# ProPrj_pico_debugger_2026-04-05.net
KiCad netlist of a schematic drawn in EasyEDA Pro
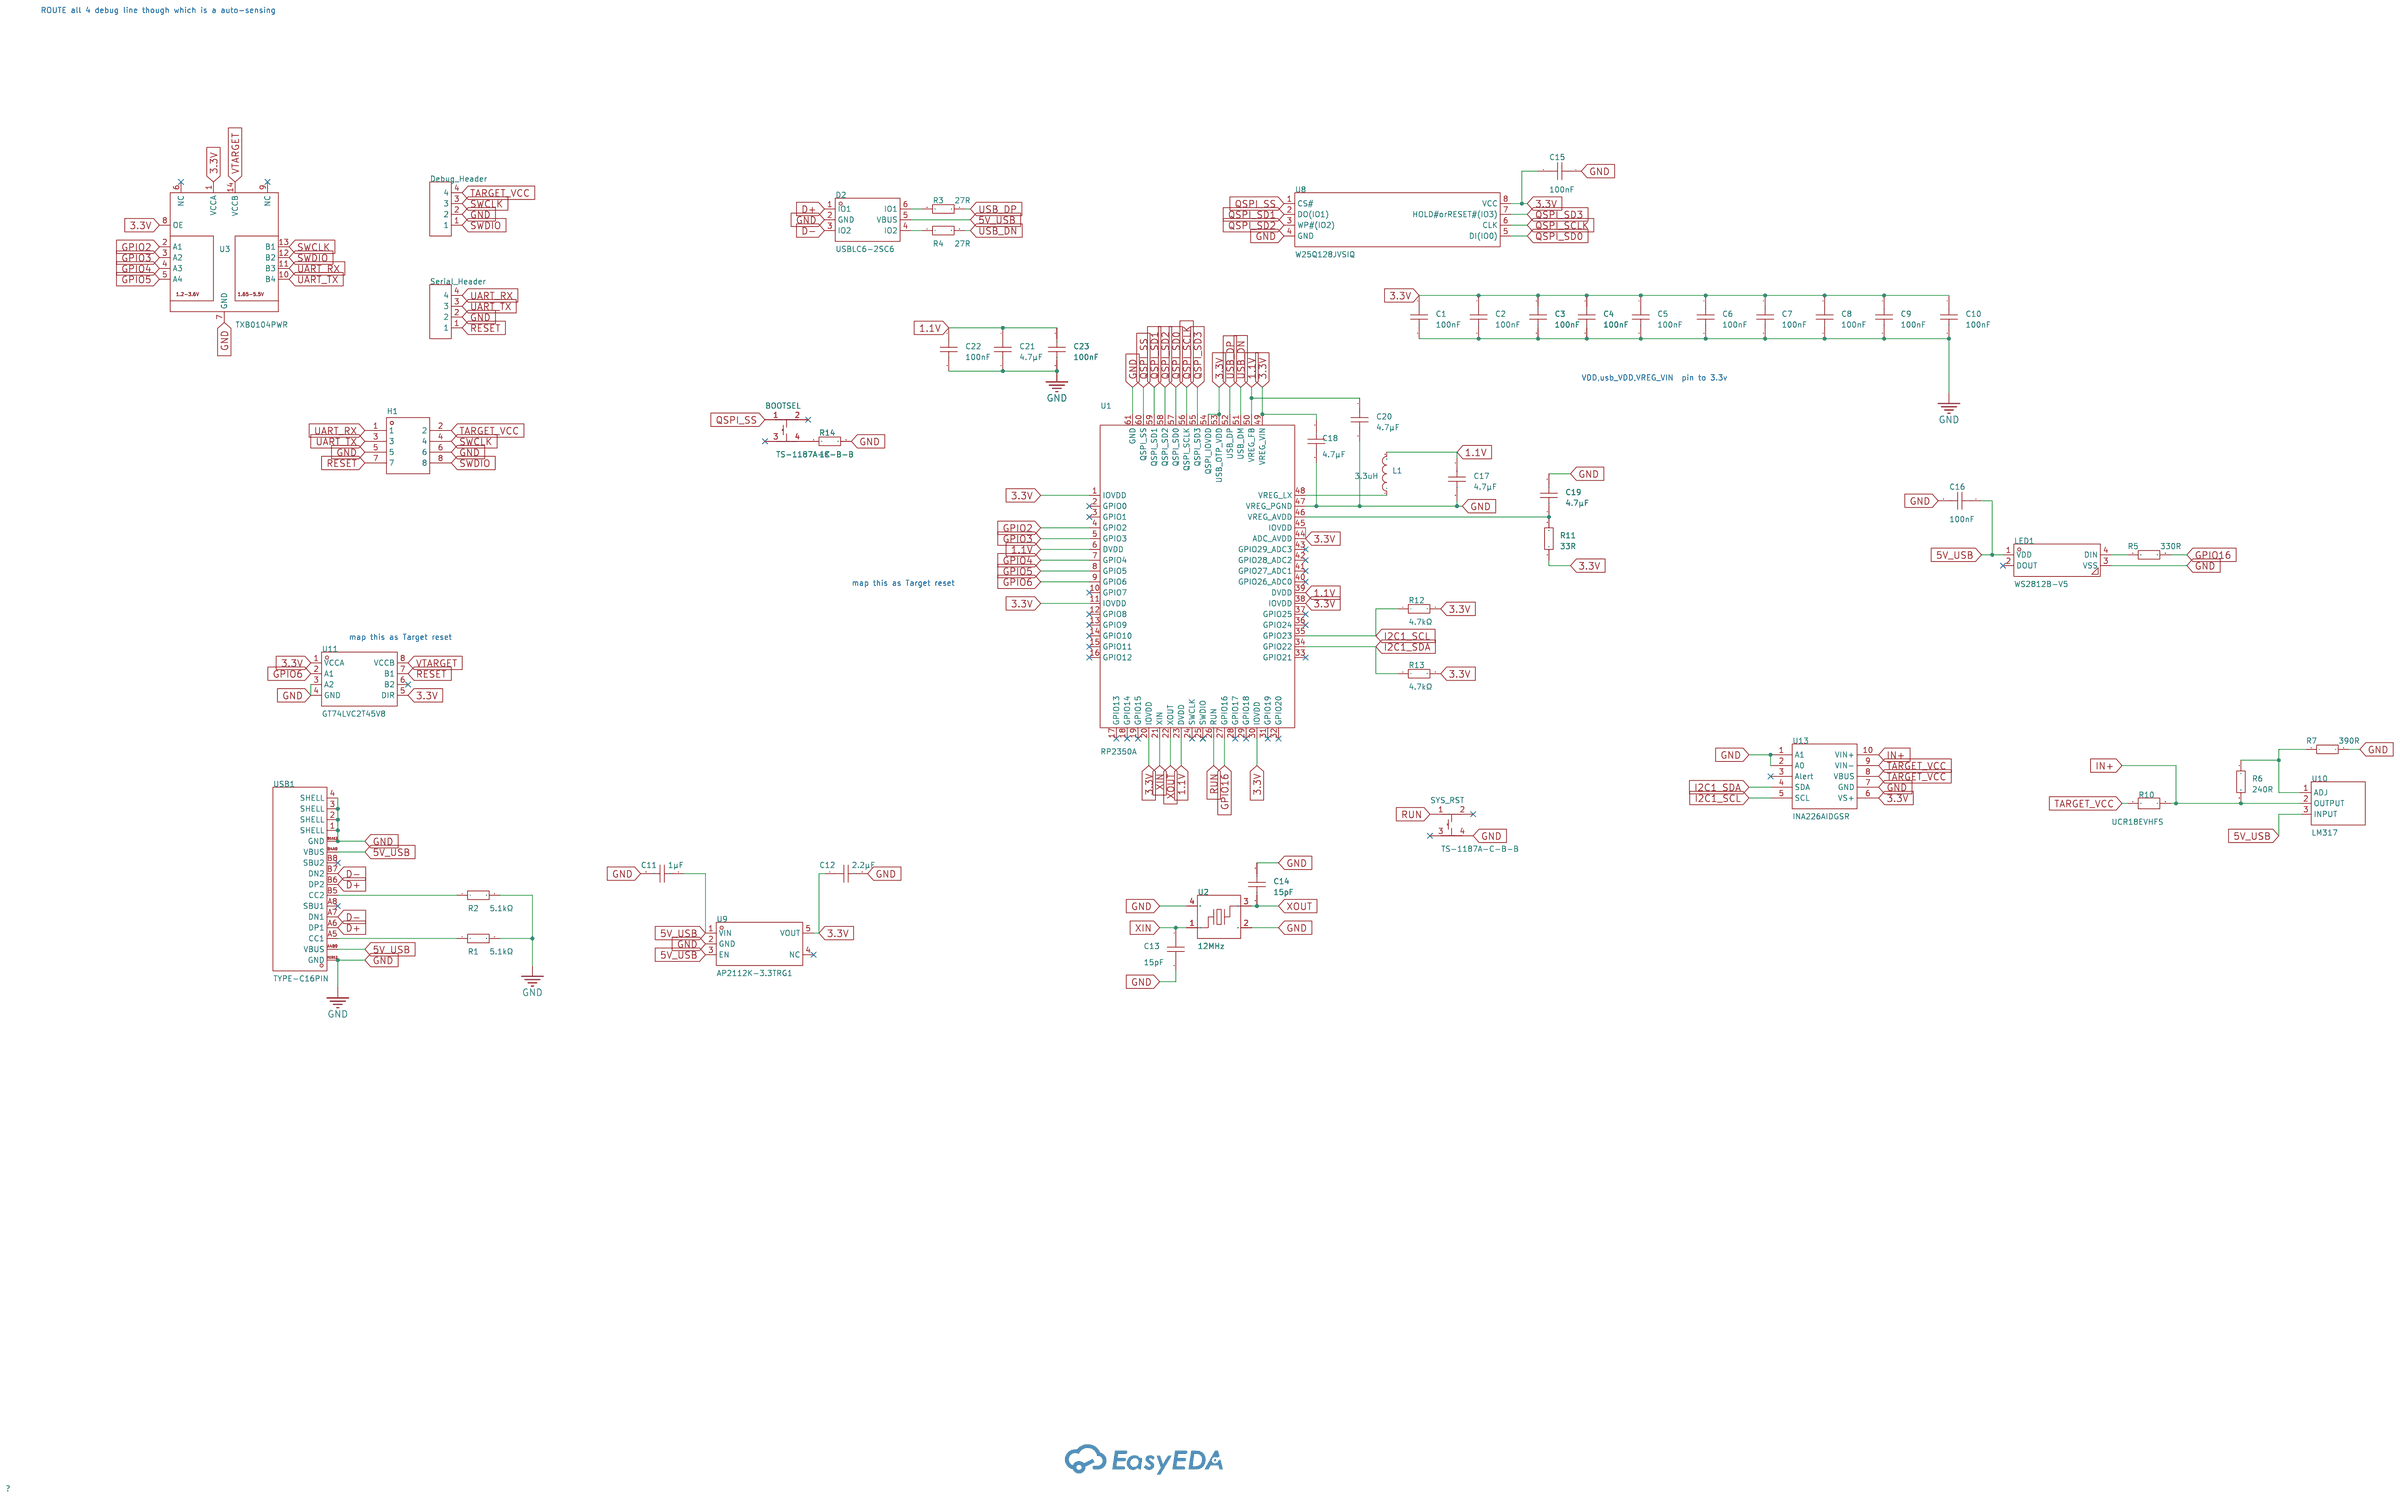
[diagram p0: schematic sheet]

(export (version "E")
  (design (tool "Eeschema 10.0.6"))
  (components
    (comp (ref "BOOTSEL")
      (value "TS-1187A-C-B-B")
      (footprint "easyedapro:SW-SMD_4P-L5.1-W5.1-P3.70-LS6.5-TL_H1.6")
      (fields (field (name "Manufacturer") "XKB Connectivity(中国星坤)"))
      (libsource (lib "easyedapro") (part "TS-1187A-C-B-B"))
    )
    (comp (ref "C1")
      (value "100nF")
      (footprint "easyedapro:C0603")
      (libsource (lib "easyedapro") (part "CAP"))
    )
    (comp (ref "C2")
      (value "100nF")
      (footprint "easyedapro:C0603")
      (libsource (lib "easyedapro") (part "CAP"))
    )
    (comp (ref "C3")
      (value "100nF")
      (footprint "easyedapro:C0603")
      (libsource (lib "easyedapro") (part "CAP"))
    )
    (comp (ref "C4")
      (value "100nF")
      (footprint "easyedapro:C0603")
      (libsource (lib "easyedapro") (part "CAP"))
    )
    (comp (ref "C5")
      (value "100nF")
      (footprint "easyedapro:C0603")
      (libsource (lib "easyedapro") (part "CAP"))
    )
    (comp (ref "C6")
      (value "100nF")
      (footprint "easyedapro:C0603")
      (libsource (lib "easyedapro") (part "CAP"))
    )
    (comp (ref "C7")
      (value "100nF")
      (footprint "easyedapro:C0603")
      (libsource (lib "easyedapro") (part "CAP"))
    )
    (comp (ref "C8")
      (value "100nF")
      (footprint "easyedapro:C0603")
      (libsource (lib "easyedapro") (part "CAP"))
    )
    (comp (ref "C9")
      (value "100nF")
      (footprint "easyedapro:C0603")
      (libsource (lib "easyedapro") (part "CAP"))
    )
    (comp (ref "C10")
      (value "100nF")
      (footprint "easyedapro:C0603")
      (libsource (lib "easyedapro") (part "CAP"))
    )
    (comp (ref "C11")
      (value "1µF")
      (footprint "easyedapro:C0603")
      (libsource (lib "easyedapro") (part "CAP"))
    )
    (comp (ref "C12")
      (value "2.2µF")
      (footprint "easyedapro:C0603")
      (libsource (lib "easyedapro") (part "CAP"))
    )
    (comp (ref "C13")
      (value "15pF")
      (footprint "easyedapro:C0603")
      (libsource (lib "easyedapro") (part "CAP"))
    )
    (comp (ref "C14")
      (value "15pF")
      (footprint "easyedapro:C0603")
      (libsource (lib "easyedapro") (part "CAP"))
    )
    (comp (ref "C15")
      (value "100nF")
      (footprint "easyedapro:C0603")
      (libsource (lib "easyedapro") (part "CAP"))
    )
    (comp (ref "C16")
      (value "100nF")
      (footprint "easyedapro:C0603")
      (libsource (lib "easyedapro") (part "CAP"))
    )
    (comp (ref "C17")
      (value "4.7µF")
      (footprint "easyedapro:C0603")
      (libsource (lib "easyedapro") (part "CAP"))
    )
    (comp (ref "C18")
      (value "4.7µF")
      (footprint "easyedapro:C0603")
      (libsource (lib "easyedapro") (part "CAP"))
    )
    (comp (ref "C19")
      (value "4.7µF")
      (footprint "easyedapro:C0603")
      (libsource (lib "easyedapro") (part "CAP"))
    )
    (comp (ref "C20")
      (value "4.7µF")
      (footprint "easyedapro:C0603")
      (libsource (lib "easyedapro") (part "CAP"))
    )
    (comp (ref "C21")
      (value "4.7µF")
      (footprint "easyedapro:C0603")
      (libsource (lib "easyedapro") (part "CAP"))
    )
    (comp (ref "C22")
      (value "100nF")
      (footprint "easyedapro:C0603")
      (libsource (lib "easyedapro") (part "CAP"))
    )
    (comp (ref "C23")
      (value "100nF")
      (footprint "easyedapro:C0603")
      (libsource (lib "easyedapro") (part "CAP"))
    )
    (comp (ref "D2")
      (value "USBLC6-2SC6")
      (footprint "easyedapro:SOT-23-6_L2.9-W1.6-P0.95-LS2.8-BL")
      (fields (field (name "Manufacturer") "TECH PUBLIC(台舟)"))
      (libsource (lib "easyedapro") (part "USBLC6-2SC6_C2827654"))
    )
    (comp (ref "Debug_Header")
      (value "~")
      (footprint "easyedapro:HDR-TH_4P-P2.54-V-M")
      (libsource (lib "easyedapro") (part "PZ254V-11-04P"))
    )
    (comp (ref "H1")
      (value "~")
      (footprint "easyedapro:HDR-TH_8P-P2.54-V-M-R2-C4-S2.54")
      (libsource (lib "easyedapro") (part "HDR-M-2.54_2x4"))
    )
    (comp (ref "L1")
      (value "3.3uH")
      (footprint "easyedapro:IND-SMD_L2.0-W1.6_AOTA-B201610S3R3-101-T")
      (fields
        (field (name "Manufacturer Part") "AOTA-B201610S3R3-101-T")
        (field (name "Manufacturer") "ABRACON")
      )
      (libsource (lib "easyedapro") (part "AOTA-B201610S3R3-101-T"))
    )
    (comp (ref "LED1")
      (value "WS2812B-V5")
      (footprint "easyedapro:LED-SMD_4P-L5.0-W5.0-LS5.4-TL-1")
      (fields (field (name "Manufacturer") "worldsemi"))
      (libsource (lib "easyedapro") (part "WS2812B-V5_C2846931"))
    )
    (comp (ref "R1")
      (value "5.1kΩ")
      (footprint "easyedapro:R0402")
      (libsource (lib "easyedapro") (part "Res"))
    )
    (comp (ref "R2")
      (value "5.1kΩ")
      (footprint "easyedapro:R0402")
      (libsource (lib "easyedapro") (part "Res"))
    )
    (comp (ref "R3") (value "27R") (footprint "easyedapro:R0402") (libsource (lib "easyedapro") (part "Res")))
    (comp (ref "R4") (value "27R") (footprint "easyedapro:R0402") (libsource (lib "easyedapro") (part "Res")))
    (comp (ref "R5")
      (value "330R")
      (footprint "easyedapro:R0402")
      (libsource (lib "easyedapro") (part "Res"))
    )
    (comp (ref "R6")
      (value "240R")
      (footprint "easyedapro:R0402")
      (libsource (lib "easyedapro") (part "Res"))
    )
    (comp (ref "R7")
      (value "390R")
      (footprint "easyedapro:R0402")
      (libsource (lib "easyedapro") (part "Res"))
    )
    (comp (ref "R10")
      (value "UCR18EVHFS")
      (footprint "easyedapro:R1206")
      (fields (field (name "Manufacturer") "ROHM(罗姆)"))
      (libsource (lib "easyedapro") (part "UCR18EVHFS"))
    )
    (comp (ref "R11")
      (value "33R")
      (footprint "easyedapro:R0402")
      (libsource (lib "easyedapro") (part "Res"))
    )
    (comp (ref "R12")
      (value "4.7kΩ")
      (footprint "easyedapro:R0402")
      (libsource (lib "easyedapro") (part "Res"))
    )
    (comp (ref "R13")
      (value "4.7kΩ")
      (footprint "easyedapro:R0402")
      (libsource (lib "easyedapro") (part "Res"))
    )
    (comp (ref "R14") (value "1K") (footprint "easyedapro:R0402") (libsource (lib "easyedapro") (part "Res")))
    (comp (ref "Serial_Header")
      (value "~")
      (footprint "easyedapro:HDR-TH_4P-P2.54-V-M")
      (libsource (lib "easyedapro") (part "PZ254V-11-04P"))
    )
    (comp (ref "SYS_RST")
      (value "TS-1187A-C-B-B")
      (footprint "easyedapro:SW-SMD_4P-L5.1-W5.1-P3.70-LS6.5-TL_H1.6")
      (fields (field (name "Manufacturer") "XKB Connectivity(中国星坤)"))
      (libsource (lib "easyedapro") (part "TS-1187A-C-B-B"))
    )
    (comp (ref "U1")
      (value "RP2350A")
      (footprint "easyedapro:QFN-60_L7.0-W7.0-P0.40-TL-EP3.4")
      (fields (field (name "Manufacturer") "Raspberry Pi(树莓派)"))
      (libsource (lib "easyedapro") (part "RP2350A_C42411118"))
    )
    (comp (ref "U2")
      (value "12MHz")
      (footprint "easyedapro:CRYSTAL-SMD_4P-L3.2-W2.5-BL")
      (fields (field (name "Manufacturer Part") "ABM8-272-T3") (field (name "Manufacturer") "ABRACON"))
      (libsource (lib "easyedapro") (part "ABM8-272-T3_C20625731"))
    )
    (comp (ref "U3")
      (value "TXB0104PWR")
      (footprint "easyedapro:TSSOP-14_L5.0-W4.4-P0.65-LS6.4-BL")
      (fields (field (name "Manufacturer") "TI(德州仪器)"))
      (libsource (lib "easyedapro") (part "TXB0104PWR"))
    )
    (comp (ref "U8")
      (value "W25Q128JVSIQ")
      (footprint "easyedapro:SOIC-8_L5.3-W5.3-P1.27-LS8.0-BL")
      (fields (field (name "Manufacturer") "Winbond(华邦)"))
      (libsource (lib "easyedapro") (part "W25Q128JVSIQ"))
    )
    (comp (ref "U9")
      (value "AP2112K-3.3TRG1")
      (footprint "easyedapro:SOT-25-5_L2.9-W1.6-P0.95-LS2.8-BL")
      (fields (field (name "Manufacturer") "DIODES(美台)"))
      (libsource (lib "easyedapro") (part "AP2112K-3.3TRG1"))
    )
    (comp (ref "U10")
      (value "LM317")
      (footprint "easyedapro:TO-252-3_L6.5-W5.9-P4.60-LS10.0-BL")
      (fields (field (name "Manufacturer") "GOODWORK(固得沃克)"))
      (libsource (lib "easyedapro") (part "LM317_C42457465"))
    )
    (comp (ref "U11")
      (value "GT74LVC2T45V8")
      (footprint "easyedapro:VSSOP-8_L2.3-W2.0-P0.50-LS3.1-BL")
      (fields (field (name "Manufacturer") "GTIC(谷泰微)"))
      (libsource (lib "easyedapro") (part "GT74LVC2T45V8"))
    )
    (comp (ref "U13")
      (value "INA226AIDGSR")
      (footprint "easyedapro:MSOP-10_L3.0-W3.0-P0.50-LS5.0-BL")
      (fields (field (name "Manufacturer") "TI(德州仪器)"))
      (libsource (lib "easyedapro") (part "INA226AIDGSR"))
    )
    (comp (ref "USB1")
      (value "TYPE-C16PIN")
      (footprint "easyedapro:USB-C-SMD_TYPE-C16PIN")
      (fields (field (name "Manufacturer") "SHOU HAN(首韩)"))
      (libsource (lib "easyedapro") (part "TYPE-C16PIN"))
    )
  )
  (nets
    (net (code "1") (name "1.1V") (class "Default")
      (node (ref "C17") (pin "1") (pinfunction "1_1") (pintype "input"))
      (node (ref "C20") (pin "1") (pinfunction "1_1") (pintype "input"))
      (node (ref "C21") (pin "1") (pinfunction "1_1") (pintype "input"))
      (node (ref "C22") (pin "1") (pinfunction "1_1") (pintype "input"))
      (node (ref "C23") (pin "1") (pinfunction "1_1") (pintype "input"))
      (node (ref "L1") (pin "2") (pinfunction "2_2") (pintype "unspecified"))
      (node (ref "U1") (pin "23") (pinfunction "DVDD_23") (pintype "unspecified"))
      (node (ref "U1") (pin "39") (pinfunction "DVDD_39") (pintype "unspecified"))
      (node (ref "U1") (pin "50") (pinfunction "VREG_FB_50") (pintype "unspecified"))
      (node (ref "U1") (pin "6") (pinfunction "DVDD_6") (pintype "unspecified"))
    )
    (net (code "2") (name "3.3V") (class "Default")
      (node (ref "C1") (pin "1") (pinfunction "1_1") (pintype "input"))
      (node (ref "C10") (pin "1") (pinfunction "1_1") (pintype "input"))
      (node (ref "C12") (pin "1") (pinfunction "1_1") (pintype "input"))
      (node (ref "C15") (pin "2") (pinfunction "2_2") (pintype "input"))
      (node (ref "C18") (pin "1") (pinfunction "1_1") (pintype "input"))
      (node (ref "C2") (pin "1") (pinfunction "1_1") (pintype "input"))
      (node (ref "C3") (pin "1") (pinfunction "1_1") (pintype "input"))
      (node (ref "C4") (pin "1") (pinfunction "1_1") (pintype "input"))
      (node (ref "C5") (pin "1") (pinfunction "1_1") (pintype "input"))
      (node (ref "C6") (pin "1") (pinfunction "1_1") (pintype "input"))
      (node (ref "C7") (pin "1") (pinfunction "1_1") (pintype "input"))
      (node (ref "C8") (pin "1") (pinfunction "1_1") (pintype "input"))
      (node (ref "C9") (pin "1") (pinfunction "1_1") (pintype "input"))
      (node (ref "R11") (pin "1") (pinfunction "1_1") (pintype "input"))
      (node (ref "R12") (pin "2") (pinfunction "2_2") (pintype "input"))
      (node (ref "R13") (pin "2") (pinfunction "2_2") (pintype "input"))
      (node (ref "U1") (pin "1") (pinfunction "IOVDD_1") (pintype "unspecified"))
      (node (ref "U1") (pin "11") (pinfunction "IOVDD_11") (pintype "unspecified"))
      (node (ref "U1") (pin "20") (pinfunction "IOVDD_20") (pintype "unspecified"))
      (node (ref "U1") (pin "30") (pinfunction "IOVDD_30") (pintype "unspecified"))
      (node (ref "U1") (pin "38") (pinfunction "IOVDD_38") (pintype "unspecified"))
      (node (ref "U1") (pin "44") (pinfunction "ADC_AVDD_44") (pintype "unspecified"))
      (node (ref "U1") (pin "45") (pinfunction "IOVDD_45") (pintype "unspecified"))
      (node (ref "U1") (pin "49") (pinfunction "VREG_VIN_49") (pintype "unspecified"))
      (node (ref "U1") (pin "53") (pinfunction "USB_OTP_VDD_53") (pintype "unspecified"))
      (node (ref "U1") (pin "54") (pinfunction "QSPI_IOVDD_54") (pintype "unspecified"))
      (node (ref "U11") (pin "1") (pinfunction "VCCA_1") (pintype "unspecified"))
      (node (ref "U11") (pin "5") (pinfunction "DIR_5") (pintype "unspecified"))
      (node (ref "U13") (pin "6") (pinfunction "VS+_6") (pintype "unspecified"))
      (node (ref "U3") (pin "1") (pinfunction "VCCA_1") (pintype "unspecified"))
      (node (ref "U3") (pin "8") (pinfunction "OE_8") (pintype "unspecified"))
      (node (ref "U8") (pin "8") (pinfunction "VCC_8") (pintype "unspecified"))
      (node (ref "U9") (pin "5") (pinfunction "VOUT_5") (pintype "unspecified"))
    )
    (net (code "3") (name "5V_USB") (class "Default")
      (node (ref "C11") (pin "1") (pinfunction "1_1") (pintype "input"))
      (node (ref "C16") (pin "1") (pinfunction "1_1") (pintype "input"))
      (node (ref "D2") (pin "5") (pinfunction "VBUS_5") (pintype "unspecified"))
      (node (ref "LED1") (pin "1") (pinfunction "VDD_1") (pintype "unspecified"))
      (node (ref "U10") (pin "3") (pinfunction "INPUT_3") (pintype "unspecified"))
      (node (ref "U9") (pin "1") (pinfunction "VIN_1") (pintype "unspecified"))
      (node (ref "U9") (pin "3") (pinfunction "EN_3") (pintype "unspecified"))
      (node (ref "USB1") (pin "A4B9") (pinfunction "VBUS_A4B9") (pintype "unspecified"))
      (node (ref "USB1") (pin "B4A9") (pinfunction "VBUS_B4A9") (pintype "unspecified"))
    )
    (net (code "4") (name "D+") (class "Default")
      (node (ref "D2") (pin "1") (pinfunction "IO1_1") (pintype "unspecified"))
      (node (ref "USB1") (pin "A6") (pinfunction "DP1_A6") (pintype "unspecified"))
      (node (ref "USB1") (pin "B6") (pinfunction "DP2_B6") (pintype "unspecified"))
    )
    (net (code "5") (name "D-") (class "Default")
      (node (ref "D2") (pin "3") (pinfunction "IO2_3") (pintype "unspecified"))
      (node (ref "USB1") (pin "A7") (pinfunction "DN1_A7") (pintype "unspecified"))
      (node (ref "USB1") (pin "B7") (pinfunction "DN2_B7") (pintype "unspecified"))
    )
    (net (code "6") (name "GND") (class "Default")
      (node (ref "C1") (pin "2") (pinfunction "2_2") (pintype "input"))
      (node (ref "C10") (pin "2") (pinfunction "2_2") (pintype "input"))
      (node (ref "C11") (pin "2") (pinfunction "2_2") (pintype "input"))
      (node (ref "C12") (pin "2") (pinfunction "2_2") (pintype "input"))
      (node (ref "C13") (pin "2") (pinfunction "2_2") (pintype "input"))
      (node (ref "C14") (pin "1") (pinfunction "1_1") (pintype "input"))
      (node (ref "C15") (pin "1") (pinfunction "1_1") (pintype "input"))
      (node (ref "C16") (pin "2") (pinfunction "2_2") (pintype "input"))
      (node (ref "C17") (pin "2") (pinfunction "2_2") (pintype "input"))
      (node (ref "C18") (pin "2") (pinfunction "2_2") (pintype "input"))
      (node (ref "C19") (pin "2") (pinfunction "2_2") (pintype "input"))
      (node (ref "C2") (pin "2") (pinfunction "2_2") (pintype "input"))
      (node (ref "C20") (pin "2") (pinfunction "2_2") (pintype "input"))
      (node (ref "C21") (pin "2") (pinfunction "2_2") (pintype "input"))
      (node (ref "C22") (pin "2") (pinfunction "2_2") (pintype "input"))
      (node (ref "C23") (pin "2") (pinfunction "2_2") (pintype "input"))
      (node (ref "C3") (pin "2") (pinfunction "2_2") (pintype "input"))
      (node (ref "C4") (pin "2") (pinfunction "2_2") (pintype "input"))
      (node (ref "C5") (pin "2") (pinfunction "2_2") (pintype "input"))
      (node (ref "C6") (pin "2") (pinfunction "2_2") (pintype "input"))
      (node (ref "C7") (pin "2") (pinfunction "2_2") (pintype "input"))
      (node (ref "C8") (pin "2") (pinfunction "2_2") (pintype "input"))
      (node (ref "C9") (pin "2") (pinfunction "2_2") (pintype "input"))
      (node (ref "D2") (pin "2") (pinfunction "GND_2") (pintype "unspecified"))
      (node (ref "Debug_Header") (pin "2") (pinfunction "2_2") (pintype "unspecified"))
      (node (ref "H1") (pin "5") (pinfunction "5_5") (pintype "input"))
      (node (ref "H1") (pin "6") (pinfunction "6_6") (pintype "input"))
      (node (ref "LED1") (pin "3") (pinfunction "VSS_3") (pintype "unspecified"))
      (node (ref "R1") (pin "2") (pinfunction "2_2") (pintype "input"))
      (node (ref "R14") (pin "2") (pinfunction "2_2") (pintype "input"))
      (node (ref "R2") (pin "2") (pinfunction "2_2") (pintype "input"))
      (node (ref "R7") (pin "2") (pinfunction "2_2") (pintype "input"))
      (node (ref "SYS_RST") (pin "4") (pinfunction "4_4") (pintype "unspecified"))
      (node (ref "Serial_Header") (pin "2") (pinfunction "2_2") (pintype "unspecified"))
      (node (ref "U1") (pin "47") (pinfunction "VREG_PGND_47") (pintype "unspecified"))
      (node (ref "U1") (pin "61") (pinfunction "GND_61") (pintype "unspecified"))
      (node (ref "U11") (pin "3") (pinfunction "A2_3") (pintype "unspecified"))
      (node (ref "U11") (pin "4") (pinfunction "GND_4") (pintype "unspecified"))
      (node (ref "U13") (pin "1") (pinfunction "A1_1") (pintype "unspecified"))
      (node (ref "U13") (pin "2") (pinfunction "A0_2") (pintype "unspecified"))
      (node (ref "U13") (pin "7") (pinfunction "GND_7") (pintype "unspecified"))
      (node (ref "U2") (pin "2") (pinfunction "GND_2") (pintype "input"))
      (node (ref "U2") (pin "4") (pinfunction "GND_4") (pintype "input"))
      (node (ref "U3") (pin "7") (pinfunction "GND_7") (pintype "unspecified"))
      (node (ref "U8") (pin "4") (pinfunction "GND_4") (pintype "unspecified"))
      (node (ref "U9") (pin "2") (pinfunction "GND_2") (pintype "unspecified"))
      (node (ref "USB1") (pin "1") (pinfunction "SHELL_1") (pintype "unspecified"))
      (node (ref "USB1") (pin "2") (pinfunction "SHELL_2") (pintype "unspecified"))
      (node (ref "USB1") (pin "3") (pinfunction "SHELL_3") (pintype "unspecified"))
      (node (ref "USB1") (pin "4") (pinfunction "SHELL_4") (pintype "unspecified"))
      (node (ref "USB1") (pin "A1B12") (pinfunction "GND_A1B12") (pintype "unspecified"))
      (node (ref "USB1") (pin "B1A12") (pinfunction "GND_B1A12") (pintype "unspecified"))
    )
    (net (code "7") (name "GPIO2") (class "Default")
      (node (ref "U1") (pin "4") (pinfunction "GPIO2_4") (pintype "unspecified"))
      (node (ref "U3") (pin "2") (pinfunction "A1_2") (pintype "unspecified"))
    )
    (net (code "8") (name "GPIO3") (class "Default")
      (node (ref "U1") (pin "5") (pinfunction "GPIO3_5") (pintype "unspecified"))
      (node (ref "U3") (pin "3") (pinfunction "A2_3") (pintype "unspecified"))
    )
    (net (code "9") (name "GPIO4") (class "Default")
      (node (ref "U1") (pin "7") (pinfunction "GPIO4_7") (pintype "unspecified"))
      (node (ref "U3") (pin "4") (pinfunction "A3_4") (pintype "unspecified"))
    )
    (net (code "10") (name "GPIO5") (class "Default")
      (node (ref "U1") (pin "8") (pinfunction "GPIO5_8") (pintype "unspecified"))
      (node (ref "U3") (pin "5") (pinfunction "A4_5") (pintype "unspecified"))
    )
    (net (code "11") (name "GPIO6") (class "Default")
      (node (ref "U1") (pin "9") (pinfunction "GPIO6_9") (pintype "unspecified"))
      (node (ref "U11") (pin "2") (pinfunction "A1_2") (pintype "unspecified"))
    )
    (net (code "12") (name "GPIO16") (class "Default")
      (node (ref "R5") (pin "2") (pinfunction "2_2") (pintype "input"))
      (node (ref "U1") (pin "27") (pinfunction "GPIO16_27") (pintype "unspecified"))
    )
    (net (code "13") (name "I2C1_SCL") (class "Default")
      (node (ref "R12") (pin "1") (pinfunction "1_1") (pintype "input"))
      (node (ref "U1") (pin "35") (pinfunction "GPIO23_35") (pintype "unspecified"))
      (node (ref "U13") (pin "5") (pinfunction "SCL_5") (pintype "unspecified"))
    )
    (net (code "14") (name "I2C1_SDA") (class "Default")
      (node (ref "R13") (pin "1") (pinfunction "1_1") (pintype "input"))
      (node (ref "U1") (pin "34") (pinfunction "GPIO22_34") (pintype "unspecified"))
      (node (ref "U13") (pin "4") (pinfunction "SDA_4") (pintype "unspecified"))
    )
    (net (code "15") (name "IN+") (class "Default")
      (node (ref "R10") (pin "2") (pinfunction "2_2") (pintype "unspecified"))
      (node (ref "R6") (pin "2") (pinfunction "2_2") (pintype "input"))
      (node (ref "U10") (pin "2") (pinfunction "OUTPUT_2") (pintype "unspecified"))
      (node (ref "U13") (pin "10") (pinfunction "VIN+_10") (pintype "unspecified"))
    )
    (net (code "16") (name "Net-(BOOTSEL-Pad4)") (class "Default")
      (node (ref "BOOTSEL") (pin "4") (pinfunction "4_4") (pintype "unspecified"))
      (node (ref "R14") (pin "1") (pinfunction "1_1") (pintype "input"))
    )
    (net (code "17") (name "Net-(D2-IO1-Pad6)") (class "Default")
      (node (ref "D2") (pin "6") (pinfunction "IO1_6") (pintype "unspecified"))
      (node (ref "R3") (pin "2") (pinfunction "2_2") (pintype "input"))
    )
    (net (code "18") (name "Net-(D2-IO2-Pad4)") (class "Default")
      (node (ref "D2") (pin "4") (pinfunction "IO2_4") (pintype "unspecified"))
      (node (ref "R4") (pin "1") (pinfunction "1_1") (pintype "input"))
    )
    (net (code "19") (name "Net-(LED1-DIN)") (class "Default")
      (node (ref "LED1") (pin "4") (pinfunction "DIN_4") (pintype "unspecified"))
      (node (ref "R5") (pin "1") (pinfunction "1_1") (pintype "input"))
    )
    (net (code "20") (name "Net-(U1-VREG_AVDD)") (class "Default")
      (node (ref "C19") (pin "1") (pinfunction "1_1") (pintype "input"))
      (node (ref "R11") (pin "2") (pinfunction "2_2") (pintype "input"))
      (node (ref "U1") (pin "46") (pinfunction "VREG_AVDD_46") (pintype "unspecified"))
    )
    (net (code "21") (name "Net-(U1-VREG_LX)") (class "Default")
      (node (ref "L1") (pin "1") (pinfunction "1_1") (pintype "unspecified"))
      (node (ref "U1") (pin "48") (pinfunction "VREG_LX_48") (pintype "unspecified"))
    )
    (net (code "22") (name "Net-(U10-ADJ)") (class "Default")
      (node (ref "R6") (pin "1") (pinfunction "1_1") (pintype "input"))
      (node (ref "R7") (pin "1") (pinfunction "1_1") (pintype "input"))
      (node (ref "U10") (pin "1") (pinfunction "ADJ_1") (pintype "unspecified"))
    )
    (net (code "23") (name "Net-(USB1-CC1)") (class "Default")
      (node (ref "R1") (pin "1") (pinfunction "1_1") (pintype "input"))
      (node (ref "USB1") (pin "A5") (pinfunction "CC1_A5") (pintype "unspecified"))
    )
    (net (code "24") (name "Net-(USB1-CC2)") (class "Default")
      (node (ref "R2") (pin "1") (pinfunction "1_1") (pintype "input"))
      (node (ref "USB1") (pin "B5") (pinfunction "CC2_B5") (pintype "unspecified"))
    )
    (net (code "25") (name "QSPI_SCLK") (class "Default")
      (node (ref "U1") (pin "56") (pinfunction "QSPI_SCLK_56") (pintype "unspecified"))
      (node (ref "U8") (pin "6") (pinfunction "CLK_6") (pintype "unspecified"))
    )
    (net (code "26") (name "QSPI_SD0") (class "Default")
      (node (ref "U1") (pin "57") (pinfunction "QSPI_SD0_57") (pintype "unspecified"))
      (node (ref "U8") (pin "5") (pinfunction "DI(IO0)_5") (pintype "unspecified"))
    )
    (net (code "27") (name "QSPI_SD1") (class "Default")
      (node (ref "U1") (pin "59") (pinfunction "QSPI_SD1_59") (pintype "unspecified"))
      (node (ref "U8") (pin "2") (pinfunction "DO(IO1)_2") (pintype "unspecified"))
    )
    (net (code "28") (name "QSPI_SD2") (class "Default")
      (node (ref "U1") (pin "58") (pinfunction "QSPI_SD2_58") (pintype "unspecified"))
      (node (ref "U8") (pin "3") (pinfunction "WP#(IO2)_3") (pintype "unspecified"))
    )
    (net (code "29") (name "QSPI_SD3") (class "Default")
      (node (ref "U1") (pin "55") (pinfunction "QSPI_SD3_55") (pintype "unspecified"))
      (node (ref "U8") (pin "7") (pinfunction "HOLD#orRESET#(IO3)_7") (pintype "unspecified"))
    )
    (net (code "30") (name "QSPI_SS") (class "Default")
      (node (ref "BOOTSEL") (pin "1") (pinfunction "1_1") (pintype "unspecified"))
      (node (ref "U1") (pin "60") (pinfunction "QSPI_SS_60") (pintype "unspecified"))
      (node (ref "U8") (pin "1") (pinfunction "CS#_1") (pintype "unspecified"))
    )
    (net (code "31") (name "RESET") (class "Default")
      (node (ref "H1") (pin "7") (pinfunction "7_7") (pintype "input"))
      (node (ref "Serial_Header") (pin "1") (pinfunction "1_1") (pintype "unspecified"))
      (node (ref "U11") (pin "7") (pinfunction "B1_7") (pintype "unspecified"))
    )
    (net (code "32") (name "RUN") (class "Default")
      (node (ref "SYS_RST") (pin "1") (pinfunction "1_1") (pintype "unspecified"))
      (node (ref "U1") (pin "26") (pinfunction "RUN_26") (pintype "unspecified"))
    )
    (net (code "33") (name "SWCLK") (class "Default")
      (node (ref "Debug_Header") (pin "3") (pinfunction "3_3") (pintype "unspecified"))
      (node (ref "H1") (pin "4") (pinfunction "4_4") (pintype "input"))
      (node (ref "U3") (pin "13") (pinfunction "B1_13") (pintype "unspecified"))
    )
    (net (code "34") (name "SWDIO") (class "Default")
      (node (ref "Debug_Header") (pin "1") (pinfunction "1_1") (pintype "unspecified"))
      (node (ref "H1") (pin "8") (pinfunction "8_8") (pintype "input"))
      (node (ref "U3") (pin "12") (pinfunction "B2_12") (pintype "unspecified"))
    )
    (net (code "35") (name "TARGET_VCC") (class "Default")
      (node (ref "Debug_Header") (pin "4") (pinfunction "4_4") (pintype "unspecified"))
      (node (ref "H1") (pin "2") (pinfunction "2_2") (pintype "input"))
      (node (ref "R10") (pin "1") (pinfunction "1_1") (pintype "unspecified"))
      (node (ref "U13") (pin "8") (pinfunction "VBUS_8") (pintype "unspecified"))
      (node (ref "U13") (pin "9") (pinfunction "VIN-_9") (pintype "unspecified"))
    )
    (net (code "36") (name "UART_RX") (class "Default")
      (node (ref "H1") (pin "1") (pinfunction "1_1") (pintype "input"))
      (node (ref "Serial_Header") (pin "4") (pinfunction "4_4") (pintype "unspecified"))
      (node (ref "U3") (pin "11") (pinfunction "B3_11") (pintype "unspecified"))
    )
    (net (code "37") (name "UART_TX") (class "Default")
      (node (ref "H1") (pin "3") (pinfunction "3_3") (pintype "input"))
      (node (ref "Serial_Header") (pin "3") (pinfunction "3_3") (pintype "unspecified"))
      (node (ref "U3") (pin "10") (pinfunction "B4_10") (pintype "unspecified"))
    )
    (net (code "38") (name "USB_DN") (class "Default")
      (node (ref "R4") (pin "2") (pinfunction "2_2") (pintype "input"))
      (node (ref "U1") (pin "51") (pinfunction "USB_DM_51") (pintype "unspecified"))
    )
    (net (code "39") (name "USB_DP") (class "Default")
      (node (ref "R3") (pin "1") (pinfunction "1_1") (pintype "input"))
      (node (ref "U1") (pin "52") (pinfunction "USB_DP_52") (pintype "unspecified"))
    )
    (net (code "40") (name "VTARGET") (class "Default")
      (node (ref "U11") (pin "8") (pinfunction "VCCB_8") (pintype "unspecified"))
      (node (ref "U3") (pin "14") (pinfunction "VCCB_14") (pintype "unspecified"))
    )
    (net (code "41") (name "XIN") (class "Default")
      (node (ref "C13") (pin "1") (pinfunction "1_1") (pintype "input"))
      (node (ref "U1") (pin "21") (pinfunction "XIN_21") (pintype "unspecified"))
      (node (ref "U2") (pin "1") (pinfunction "1_1") (pintype "input"))
    )
    (net (code "42") (name "XOUT") (class "Default")
      (node (ref "C14") (pin "2") (pinfunction "2_2") (pintype "input"))
      (node (ref "U1") (pin "22") (pinfunction "XOUT_22") (pintype "unspecified"))
      (node (ref "U2") (pin "3") (pinfunction "3_3") (pintype "input"))
    )
    (net (code "43") (name "unconnected-(BOOTSEL-Pad2)") (class "Default")
      (node (ref "BOOTSEL") (pin "2") (pinfunction "2_2") (pintype "unspecified+no_connect"))
    )
    (net (code "44") (name "unconnected-(BOOTSEL-Pad3)") (class "Default")
      (node (ref "BOOTSEL") (pin "3") (pinfunction "3_3") (pintype "unspecified+no_connect"))
    )
    (net (code "45") (name "unconnected-(LED1-DOUT-Pad2)") (class "Default")
      (node (ref "LED1") (pin "2") (pinfunction "DOUT_2") (pintype "unspecified+no_connect"))
    )
    (net (code "46") (name "unconnected-(SYS_RST-Pad2)") (class "Default")
      (node (ref "SYS_RST") (pin "2") (pinfunction "2_2") (pintype "unspecified+no_connect"))
    )
    (net (code "47") (name "unconnected-(SYS_RST-Pad3)") (class "Default")
      (node (ref "SYS_RST") (pin "3") (pinfunction "3_3") (pintype "unspecified+no_connect"))
    )
    (net (code "48") (name "unconnected-(U1-GPIO0-Pad2)") (class "Default")
      (node (ref "U1") (pin "2") (pinfunction "GPIO0_2") (pintype "unspecified+no_connect"))
    )
    (net (code "49") (name "unconnected-(U1-GPIO1-Pad3)") (class "Default")
      (node (ref "U1") (pin "3") (pinfunction "GPIO1_3") (pintype "unspecified+no_connect"))
    )
    (net (code "50") (name "unconnected-(U1-GPIO7-Pad10)") (class "Default")
      (node (ref "U1") (pin "10") (pinfunction "GPIO7_10") (pintype "unspecified+no_connect"))
    )
    (net (code "51") (name "unconnected-(U1-GPIO8-Pad12)") (class "Default")
      (node (ref "U1") (pin "12") (pinfunction "GPIO8_12") (pintype "unspecified+no_connect"))
    )
    (net (code "52") (name "unconnected-(U1-GPIO9-Pad13)") (class "Default")
      (node (ref "U1") (pin "13") (pinfunction "GPIO9_13") (pintype "unspecified+no_connect"))
    )
    (net (code "53") (name "unconnected-(U1-GPIO10-Pad14)") (class "Default")
      (node (ref "U1") (pin "14") (pinfunction "GPIO10_14") (pintype "unspecified+no_connect"))
    )
    (net (code "54") (name "unconnected-(U1-GPIO11-Pad15)") (class "Default")
      (node (ref "U1") (pin "15") (pinfunction "GPIO11_15") (pintype "unspecified+no_connect"))
    )
    (net (code "55") (name "unconnected-(U1-GPIO12-Pad16)") (class "Default")
      (node (ref "U1") (pin "16") (pinfunction "GPIO12_16") (pintype "unspecified+no_connect"))
    )
    (net (code "56") (name "unconnected-(U1-GPIO13-Pad17)") (class "Default")
      (node (ref "U1") (pin "17") (pinfunction "GPIO13_17") (pintype "unspecified+no_connect"))
    )
    (net (code "57") (name "unconnected-(U1-GPIO14-Pad18)") (class "Default")
      (node (ref "U1") (pin "18") (pinfunction "GPIO14_18") (pintype "unspecified+no_connect"))
    )
    (net (code "58") (name "unconnected-(U1-GPIO15-Pad19)") (class "Default")
      (node (ref "U1") (pin "19") (pinfunction "GPIO15_19") (pintype "unspecified+no_connect"))
    )
    (net (code "59") (name "unconnected-(U1-GPIO17-Pad28)") (class "Default")
      (node (ref "U1") (pin "28") (pinfunction "GPIO17_28") (pintype "unspecified+no_connect"))
    )
    (net (code "60") (name "unconnected-(U1-GPIO18-Pad29)") (class "Default")
      (node (ref "U1") (pin "29") (pinfunction "GPIO18_29") (pintype "unspecified+no_connect"))
    )
    (net (code "61") (name "unconnected-(U1-GPIO19-Pad31)") (class "Default")
      (node (ref "U1") (pin "31") (pinfunction "GPIO19_31") (pintype "unspecified+no_connect"))
    )
    (net (code "62") (name "unconnected-(U1-GPIO20-Pad32)") (class "Default")
      (node (ref "U1") (pin "32") (pinfunction "GPIO20_32") (pintype "unspecified+no_connect"))
    )
    (net (code "63") (name "unconnected-(U1-GPIO21-Pad33)") (class "Default")
      (node (ref "U1") (pin "33") (pinfunction "GPIO21_33") (pintype "unspecified+no_connect"))
    )
    (net (code "64") (name "unconnected-(U1-GPIO24-Pad36)") (class "Default")
      (node (ref "U1") (pin "36") (pinfunction "GPIO24_36") (pintype "unspecified+no_connect"))
    )
    (net (code "65") (name "unconnected-(U1-GPIO25-Pad37)") (class "Default")
      (node (ref "U1") (pin "37") (pinfunction "GPIO25_37") (pintype "unspecified+no_connect"))
    )
    (net (code "66") (name "unconnected-(U1-GPIO26_ADC0-Pad40)") (class "Default")
      (node (ref "U1") (pin "40") (pinfunction "GPIO26_ADC0_40") (pintype "unspecified+no_connect"))
    )
    (net (code "67") (name "unconnected-(U1-GPIO27_ADC1-Pad41)") (class "Default")
      (node (ref "U1") (pin "41") (pinfunction "GPIO27_ADC1_41") (pintype "unspecified+no_connect"))
    )
    (net (code "68") (name "unconnected-(U1-GPIO28_ADC2-Pad42)") (class "Default")
      (node (ref "U1") (pin "42") (pinfunction "GPIO28_ADC2_42") (pintype "unspecified+no_connect"))
    )
    (net (code "69") (name "unconnected-(U1-GPIO29_ADC3-Pad43)") (class "Default")
      (node (ref "U1") (pin "43") (pinfunction "GPIO29_ADC3_43") (pintype "unspecified+no_connect"))
    )
    (net (code "70") (name "unconnected-(U1-SWCLK-Pad24)") (class "Default")
      (node (ref "U1") (pin "24") (pinfunction "SWCLK_24") (pintype "unspecified+no_connect"))
    )
    (net (code "71") (name "unconnected-(U1-SWDIO-Pad25)") (class "Default")
      (node (ref "U1") (pin "25") (pinfunction "SWDIO_25") (pintype "unspecified+no_connect"))
    )
    (net (code "72") (name "unconnected-(U3-NC-Pad6)") (class "Default")
      (node (ref "U3") (pin "6") (pinfunction "NC_6") (pintype "unspecified+no_connect"))
    )
    (net (code "73") (name "unconnected-(U3-NC-Pad9)") (class "Default")
      (node (ref "U3") (pin "9") (pinfunction "NC_9") (pintype "unspecified+no_connect"))
    )
    (net (code "74") (name "unconnected-(U9-NC-Pad4)") (class "Default")
      (node (ref "U9") (pin "4") (pinfunction "NC_4") (pintype "unspecified+no_connect"))
    )
    (net (code "75") (name "unconnected-(U11-B2-Pad6)") (class "Default")
      (node (ref "U11") (pin "6") (pinfunction "B2_6") (pintype "unspecified+no_connect"))
    )
    (net (code "76") (name "unconnected-(U13-Alert-Pad3)") (class "Default")
      (node (ref "U13") (pin "3") (pinfunction "Alert_3") (pintype "unspecified+no_connect"))
    )
    (net (code "77") (name "unconnected-(USB1-SBU1-PadA8)") (class "Default")
      (node (ref "USB1") (pin "A8") (pinfunction "SBU1_A8") (pintype "unspecified+no_connect"))
    )
    (net (code "78") (name "unconnected-(USB1-SBU2-PadB8)") (class "Default")
      (node (ref "USB1") (pin "B8") (pinfunction "SBU2_B8") (pintype "unspecified+no_connect"))
    )
  )
)
